# Power.net
KiCad netlist of a schematic drawn in Altium Designer
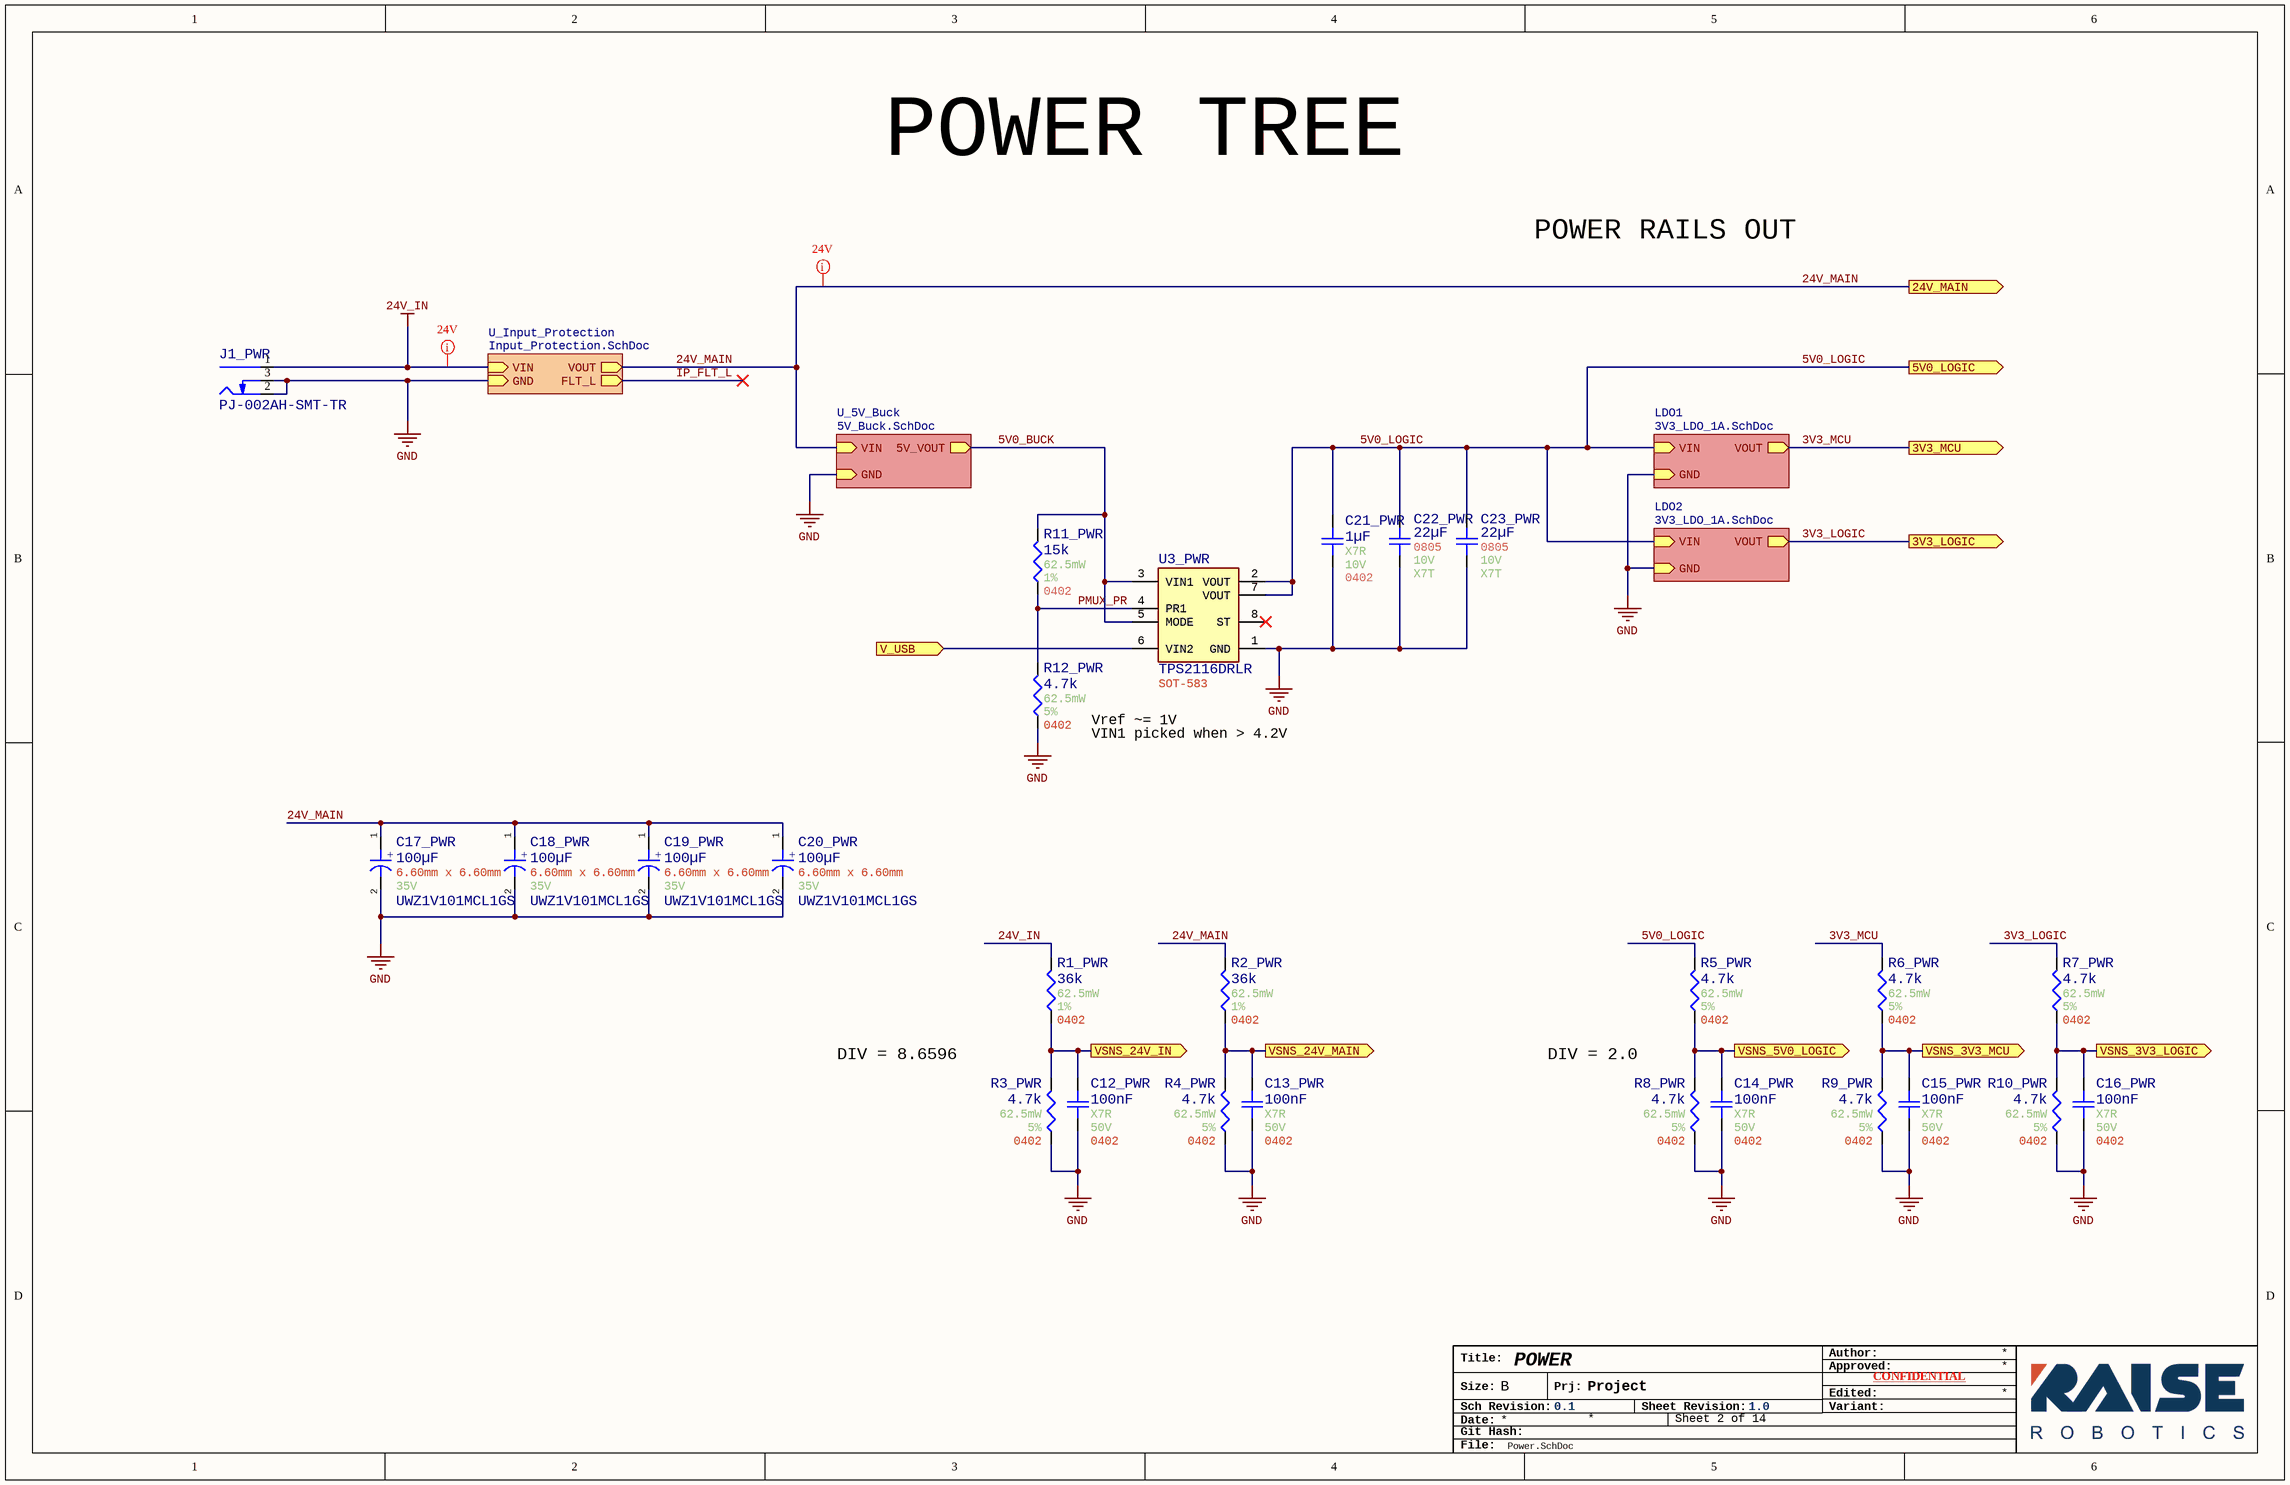
[diagram p0: Power.SchDoc]

(export (version "E")
  (design (tool "Eeschema 10.0.6"))
  (components
    (comp (ref "C12_PWR")
      (value "100nF")
      (footprint "Generic 0402 capacitor")
      (fields
        (field (name "TEMPERATURE COEFFICIENT") "X7R")
        (field (name "VOLTAGE RATING") "50V")
        (field (name "CASE/PACKAGE") "0402")
        (field (name "TOLERANCE") "10%")
        (field (name "Comment") "GRT155R71H104KE01D")
      )
      (libsource (lib "Raise Robotics") (part "Unpolarized Capacitor"))
    )
    (comp (ref "C13_PWR")
      (value "100nF")
      (footprint "Generic 0402 capacitor")
      (fields
        (field (name "TEMPERATURE COEFFICIENT") "X7R")
        (field (name "VOLTAGE RATING") "50V")
        (field (name "CASE/PACKAGE") "0402")
        (field (name "TOLERANCE") "10%")
        (field (name "Comment") "GRT155R71H104KE01D")
      )
      (libsource (lib "Raise Robotics") (part "Unpolarized Capacitor"))
    )
    (comp (ref "C14_PWR")
      (value "100nF")
      (footprint "Generic 0402 capacitor")
      (fields
        (field (name "TEMPERATURE COEFFICIENT") "X7R")
        (field (name "VOLTAGE RATING") "50V")
        (field (name "CASE/PACKAGE") "0402")
        (field (name "TOLERANCE") "10%")
        (field (name "Comment") "GRT155R71H104KE01D")
      )
      (libsource (lib "Raise Robotics") (part "Unpolarized Capacitor"))
    )
    (comp (ref "C15_PWR")
      (value "100nF")
      (footprint "Generic 0402 capacitor")
      (fields
        (field (name "TEMPERATURE COEFFICIENT") "X7R")
        (field (name "VOLTAGE RATING") "50V")
        (field (name "CASE/PACKAGE") "0402")
        (field (name "TOLERANCE") "10%")
        (field (name "Comment") "GRT155R71H104KE01D")
      )
      (libsource (lib "Raise Robotics") (part "Unpolarized Capacitor"))
    )
    (comp (ref "C16_PWR")
      (value "100nF")
      (footprint "Generic 0402 capacitor")
      (fields
        (field (name "TEMPERATURE COEFFICIENT") "X7R")
        (field (name "VOLTAGE RATING") "50V")
        (field (name "CASE/PACKAGE") "0402")
        (field (name "TOLERANCE") "10%")
        (field (name "Comment") "GRT155R71H104KE01D")
      )
      (libsource (lib "Raise Robotics") (part "Unpolarized Capacitor"))
    )
    (comp (ref "C17_PWR")
      (value "UWZ1V101MCL1GS")
      (footprint "UWZ1V101MCL1GS")
      (fields
        (field (name "ALTIUM_VALUE") "100µF")
        (field (name "CASE/PACKAGE") "6.60mm x 6.60mm")
        (field (name "VOLTAGE RATING") "35V")
      )
      (libsource (lib "Raise Robotics") (part "Polarized Capacitor Pin1+"))
    )
    (comp (ref "C18_PWR")
      (value "UWZ1V101MCL1GS")
      (footprint "UWZ1V101MCL1GS")
      (fields
        (field (name "ALTIUM_VALUE") "100µF")
        (field (name "CASE/PACKAGE") "6.60mm x 6.60mm")
        (field (name "VOLTAGE RATING") "35V")
      )
      (libsource (lib "Raise Robotics") (part "Polarized Capacitor Pin1+"))
    )
    (comp (ref "C19_PWR")
      (value "UWZ1V101MCL1GS")
      (footprint "UWZ1V101MCL1GS")
      (fields
        (field (name "ALTIUM_VALUE") "100µF")
        (field (name "CASE/PACKAGE") "6.60mm x 6.60mm")
        (field (name "VOLTAGE RATING") "35V")
      )
      (libsource (lib "Raise Robotics") (part "Polarized Capacitor Pin1+"))
    )
    (comp (ref "C20_PWR")
      (value "UWZ1V101MCL1GS")
      (footprint "UWZ1V101MCL1GS")
      (fields
        (field (name "ALTIUM_VALUE") "100µF")
        (field (name "CASE/PACKAGE") "6.60mm x 6.60mm")
        (field (name "VOLTAGE RATING") "35V")
      )
      (libsource (lib "Raise Robotics") (part "Polarized Capacitor Pin1+"))
    )
    (comp (ref "C21_PWR")
      (value "1µF")
      (footprint "Generic 0402 capacitor")
      (description "Cap Cer 1UF 20V X7T 0402")
      (fields
        (field (name "TEMPERATURE COEFFICIENT") "X7R")
        (field (name "VOLTAGE RATING") "10V")
        (field (name "CASE/PACKAGE") "0402")
        (field (name "TOLERANCE") "20%")
        (field (name "Comment") "MAASL105CD7105MFCA01")
      )
      (libsource (lib "Raise Robotics") (part "Unpolarized Capacitor"))
    )
    (comp (ref "C22_PWR")
      (value "22µF")
      (footprint "Generic 0805 Cap")
      (description "22 µF ±20% 10V Ceramic Capacitor X7T 0805 (2012 Metric)")
      (fields
        (field (name "TEMPERATURE COEFFICIENT") "X7T")
        (field (name "VOLTAGE RATING") "10V")
        (field (name "CASE/PACKAGE") "0805")
        (field (name "TOLERANCE") "20%")
        (field (name "Comment") "GRT21BD71A226ME13L")
      )
      (libsource (lib "Raise Robotics") (part "Unpolarized Capacitor"))
    )
    (comp (ref "C23_PWR")
      (value "22µF")
      (footprint "Generic 0805 Cap")
      (description "22 µF ±20% 10V Ceramic Capacitor X7T 0805 (2012 Metric)")
      (fields
        (field (name "TEMPERATURE COEFFICIENT") "X7T")
        (field (name "VOLTAGE RATING") "10V")
        (field (name "CASE/PACKAGE") "0805")
        (field (name "TOLERANCE") "20%")
        (field (name "Comment") "GRT21BD71A226ME13L")
      )
      (libsource (lib "Raise Robotics") (part "Unpolarized Capacitor"))
    )
    (comp (ref "J1_PWR")
      (value "PJ-002AH-SMT-TR")
      (footprint "CUI PJ-002AH-SMT-TR")
      (description "CONN PWR JACK 2X5.5MM SOLDER")
      (fields (field (name "MANUFACTURER") "CUI Devices"))
      (libsource (lib "Celestial Altium Library - altium_library") (part "Barrel Connector"))
    )
    (comp (ref "R1_PWR")
      (value "36k")
      (footprint "Generic 0402 Resistor")
      (fields
        (field (name "POWER") "62.5mW")
        (field (name "TOLERANCE") "1%")
        (field (name "CASE/PACKAGE") "0402")
        (field (name "Comment") "AC0402FR-0736KL")
      )
      (libsource (lib "Raise Robotics") (part "Resistor"))
    )
    (comp (ref "R2_PWR")
      (value "36k")
      (footprint "Generic 0402 Resistor")
      (fields
        (field (name "POWER") "62.5mW")
        (field (name "TOLERANCE") "1%")
        (field (name "CASE/PACKAGE") "0402")
        (field (name "Comment") "AC0402FR-0736KL")
      )
      (libsource (lib "Raise Robotics") (part "Resistor"))
    )
    (comp (ref "R3_PWR")
      (value "4.7k")
      (footprint "Generic 0402 Resistor")
      (fields
        (field (name "POWER") "62.5mW")
        (field (name "TOLERANCE") "5%")
        (field (name "CASE/PACKAGE") "0402")
        (field (name "MANUFACTURER PART NUMBER") "Blank")
        (field (name "Comment") "WR04X472JTL")
      )
      (libsource (lib "Raise Robotics") (part "Resistor"))
    )
    (comp (ref "R4_PWR")
      (value "4.7k")
      (footprint "Generic 0402 Resistor")
      (fields
        (field (name "POWER") "62.5mW")
        (field (name "TOLERANCE") "5%")
        (field (name "CASE/PACKAGE") "0402")
        (field (name "MANUFACTURER PART NUMBER") "Blank")
        (field (name "Comment") "WR04X472JTL")
      )
      (libsource (lib "Raise Robotics") (part "Resistor"))
    )
    (comp (ref "R5_PWR")
      (value "4.7k")
      (footprint "Generic 0402 Resistor")
      (fields
        (field (name "POWER") "62.5mW")
        (field (name "TOLERANCE") "5%")
        (field (name "CASE/PACKAGE") "0402")
        (field (name "MANUFACTURER PART NUMBER") "Blank")
        (field (name "Comment") "WR04X472JTL")
      )
      (libsource (lib "Raise Robotics") (part "Resistor"))
    )
    (comp (ref "R6_PWR")
      (value "4.7k")
      (footprint "Generic 0402 Resistor")
      (fields
        (field (name "POWER") "62.5mW")
        (field (name "TOLERANCE") "5%")
        (field (name "CASE/PACKAGE") "0402")
        (field (name "MANUFACTURER PART NUMBER") "Blank")
        (field (name "Comment") "WR04X472JTL")
      )
      (libsource (lib "Raise Robotics") (part "Resistor"))
    )
    (comp (ref "R7_PWR")
      (value "4.7k")
      (footprint "Generic 0402 Resistor")
      (fields
        (field (name "POWER") "62.5mW")
        (field (name "TOLERANCE") "5%")
        (field (name "CASE/PACKAGE") "0402")
        (field (name "MANUFACTURER PART NUMBER") "Blank")
        (field (name "Comment") "WR04X472JTL")
      )
      (libsource (lib "Raise Robotics") (part "Resistor"))
    )
    (comp (ref "R8_PWR")
      (value "4.7k")
      (footprint "Generic 0402 Resistor")
      (fields
        (field (name "POWER") "62.5mW")
        (field (name "TOLERANCE") "5%")
        (field (name "CASE/PACKAGE") "0402")
        (field (name "MANUFACTURER PART NUMBER") "Blank")
        (field (name "Comment") "WR04X472JTL")
      )
      (libsource (lib "Raise Robotics") (part "Resistor"))
    )
    (comp (ref "R9_PWR")
      (value "4.7k")
      (footprint "Generic 0402 Resistor")
      (fields
        (field (name "POWER") "62.5mW")
        (field (name "TOLERANCE") "5%")
        (field (name "CASE/PACKAGE") "0402")
        (field (name "MANUFACTURER PART NUMBER") "Blank")
        (field (name "Comment") "WR04X472JTL")
      )
      (libsource (lib "Raise Robotics") (part "Resistor"))
    )
    (comp (ref "R10_PWR")
      (value "4.7k")
      (footprint "Generic 0402 Resistor")
      (fields
        (field (name "POWER") "62.5mW")
        (field (name "TOLERANCE") "5%")
        (field (name "CASE/PACKAGE") "0402")
        (field (name "MANUFACTURER PART NUMBER") "Blank")
        (field (name "Comment") "WR04X472JTL")
      )
      (libsource (lib "Raise Robotics") (part "Resistor"))
    )
    (comp (ref "R11_PWR")
      (value "15k")
      (footprint "Generic 0402 Resistor")
      (description "Res Thick Film 0402 15K Ohm 1% 0.063W(1/16W) ±100ppm/°C Pad SMD T/R Automotive AEC-Q200")
      (fields
        (field (name "POWER") "62.5mW")
        (field (name "TOLERANCE") "1%")
        (field (name "CASE/PACKAGE") "0402")
        (field (name "Comment") "AC0402FR-1315KL")
      )
      (libsource (lib "Raise Robotics") (part "Resistor"))
    )
    (comp (ref "R12_PWR")
      (value "4.7k")
      (footprint "Generic 0402 Resistor")
      (fields
        (field (name "POWER") "62.5mW")
        (field (name "TOLERANCE") "5%")
        (field (name "CASE/PACKAGE") "0402")
        (field (name "MANUFACTURER PART NUMBER") "Blank")
        (field (name "Comment") "WR04X472JTL")
      )
      (libsource (lib "Raise Robotics") (part "Resistor"))
    )
    (comp (ref "U3_PWR")
      (value "TPS2116DRLR")
      (footprint "SOT-583_1.3x2.2x0.6mm_P0.5mm")
      (description "1.6-V to 5.5-V, 40-mΩ, 2.5-A, low-IQ, priority power multiplexer ; 8-SOT-5X3 -40 to 125")
      (fields (field (name "CASE/PACKAGE") "SOT-583"))
      (libsource (lib "Raise Robotics") (part "TPS2116DRLR"))
    )
  )
  (nets
    (net (code "1") (name "/3V3_LOGIC") (class "Default")
      (node (ref "R7_PWR") (pin "2") (pinfunction "2_2") (pintype "passive"))
    )
    (net (code "2") (name "/3V3_MCU") (class "Default")
      (node (ref "R6_PWR") (pin "2") (pinfunction "2_2") (pintype "passive"))
    )
    (net (code "3") (name "/5V0_BUCK") (class "Default")
      (node (ref "R11_PWR") (pin "2") (pinfunction "2_2") (pintype "passive"))
      (node (ref "U3_PWR") (pin "3") (pinfunction "VIN1_3") (pintype "passive"))
      (node (ref "U3_PWR") (pin "5") (pinfunction "MODE_5") (pintype "passive"))
    )
    (net (code "4") (name "/5V0_LOGIC") (class "Default")
      (node (ref "C21_PWR") (pin "2") (pinfunction "2_2") (pintype "passive"))
      (node (ref "C22_PWR") (pin "2") (pinfunction "2_2") (pintype "passive"))
      (node (ref "C23_PWR") (pin "2") (pinfunction "2_2") (pintype "passive"))
      (node (ref "R5_PWR") (pin "2") (pinfunction "2_2") (pintype "passive"))
      (node (ref "U3_PWR") (pin "2") (pinfunction "VOUT_2") (pintype "passive"))
      (node (ref "U3_PWR") (pin "7") (pinfunction "VOUT_7") (pintype "passive"))
    )
    (net (code "5") (name "/24V_MAIN") (class "Default")
      (node (ref "C17_PWR") (pin "1") (pinfunction "1_1") (pintype "passive"))
      (node (ref "C18_PWR") (pin "1") (pinfunction "1_1") (pintype "passive"))
      (node (ref "C19_PWR") (pin "1") (pinfunction "1_1") (pintype "passive"))
      (node (ref "C20_PWR") (pin "1") (pinfunction "1_1") (pintype "passive"))
      (node (ref "R2_PWR") (pin "2") (pinfunction "2_2") (pintype "passive"))
    )
    (net (code "7") (name "/PMUX_PR") (class "Default")
      (node (ref "R11_PWR") (pin "1") (pinfunction "1_1") (pintype "passive"))
      (node (ref "R12_PWR") (pin "2") (pinfunction "2_2") (pintype "passive"))
      (node (ref "U3_PWR") (pin "4") (pinfunction "PR1_4") (pintype "passive"))
    )
    (net (code "8") (name "/VSNS_3V3_LOGIC") (class "Default")
      (node (ref "C16_PWR") (pin "1") (pinfunction "1_1") (pintype "passive"))
      (node (ref "R10_PWR") (pin "2") (pinfunction "2_2") (pintype "passive"))
      (node (ref "R7_PWR") (pin "1") (pinfunction "1_1") (pintype "passive"))
    )
    (net (code "9") (name "/VSNS_3V3_MCU") (class "Default")
      (node (ref "C15_PWR") (pin "1") (pinfunction "1_1") (pintype "passive"))
      (node (ref "R6_PWR") (pin "1") (pinfunction "1_1") (pintype "passive"))
      (node (ref "R9_PWR") (pin "2") (pinfunction "2_2") (pintype "passive"))
    )
    (net (code "10") (name "/VSNS_5V0_LOGIC") (class "Default")
      (node (ref "C14_PWR") (pin "1") (pinfunction "1_1") (pintype "passive"))
      (node (ref "R5_PWR") (pin "1") (pinfunction "1_1") (pintype "passive"))
      (node (ref "R8_PWR") (pin "2") (pinfunction "2_2") (pintype "passive"))
    )
    (net (code "11") (name "/VSNS_24V_IN") (class "Default")
      (node (ref "C12_PWR") (pin "1") (pinfunction "1_1") (pintype "passive"))
      (node (ref "R1_PWR") (pin "1") (pinfunction "1_1") (pintype "passive"))
      (node (ref "R3_PWR") (pin "2") (pinfunction "2_2") (pintype "passive"))
    )
    (net (code "12") (name "/VSNS_24V_MAIN") (class "Default")
      (node (ref "C13_PWR") (pin "1") (pinfunction "1_1") (pintype "passive"))
      (node (ref "R2_PWR") (pin "1") (pinfunction "1_1") (pintype "passive"))
      (node (ref "R4_PWR") (pin "2") (pinfunction "2_2") (pintype "passive"))
    )
    (net (code "13") (name "/V_USB") (class "Default")
      (node (ref "U3_PWR") (pin "6") (pinfunction "VIN2_6") (pintype "passive"))
    )
    (net (code "14") (name "24V_IN") (class "Default")
      (node (ref "J1_PWR") (pin "1") (pinfunction "Centre_1") (pintype "passive"))
      (node (ref "R1_PWR") (pin "2") (pinfunction "2_2") (pintype "passive"))
    )
    (net (code "15") (name "GND") (class "Default")
      (node (ref "C12_PWR") (pin "2") (pinfunction "2_2") (pintype "passive"))
      (node (ref "C13_PWR") (pin "2") (pinfunction "2_2") (pintype "passive"))
      (node (ref "C14_PWR") (pin "2") (pinfunction "2_2") (pintype "passive"))
      (node (ref "C15_PWR") (pin "2") (pinfunction "2_2") (pintype "passive"))
      (node (ref "C16_PWR") (pin "2") (pinfunction "2_2") (pintype "passive"))
      (node (ref "C17_PWR") (pin "2") (pinfunction "2_2") (pintype "passive"))
      (node (ref "C18_PWR") (pin "2") (pinfunction "2_2") (pintype "passive"))
      (node (ref "C19_PWR") (pin "2") (pinfunction "2_2") (pintype "passive"))
      (node (ref "C20_PWR") (pin "2") (pinfunction "2_2") (pintype "passive"))
      (node (ref "C21_PWR") (pin "1") (pinfunction "1_1") (pintype "passive"))
      (node (ref "C22_PWR") (pin "1") (pinfunction "1_1") (pintype "passive"))
      (node (ref "C23_PWR") (pin "1") (pinfunction "1_1") (pintype "passive"))
      (node (ref "J1_PWR") (pin "2") (pinfunction "Outer_2") (pintype "passive"))
      (node (ref "J1_PWR") (pin "3") (pinfunction "SW_3") (pintype "passive"))
      (node (ref "R10_PWR") (pin "1") (pinfunction "1_1") (pintype "passive"))
      (node (ref "R12_PWR") (pin "1") (pinfunction "1_1") (pintype "passive"))
      (node (ref "R3_PWR") (pin "1") (pinfunction "1_1") (pintype "passive"))
      (node (ref "R4_PWR") (pin "1") (pinfunction "1_1") (pintype "passive"))
      (node (ref "R8_PWR") (pin "1") (pinfunction "1_1") (pintype "passive"))
      (node (ref "R9_PWR") (pin "1") (pinfunction "1_1") (pintype "passive"))
      (node (ref "U3_PWR") (pin "1") (pinfunction "GND_1") (pintype "passive"))
    )
    (net (code "16") (name "unconnected-(U3_PWR-ST-Pad8)") (class "Default")
      (node (ref "U3_PWR") (pin "8") (pinfunction "ST_8") (pintype "passive+no_connect"))
    )
  )
)
